# main_scheme.net
KiCad netlist of a schematic drawn in Altium Designer
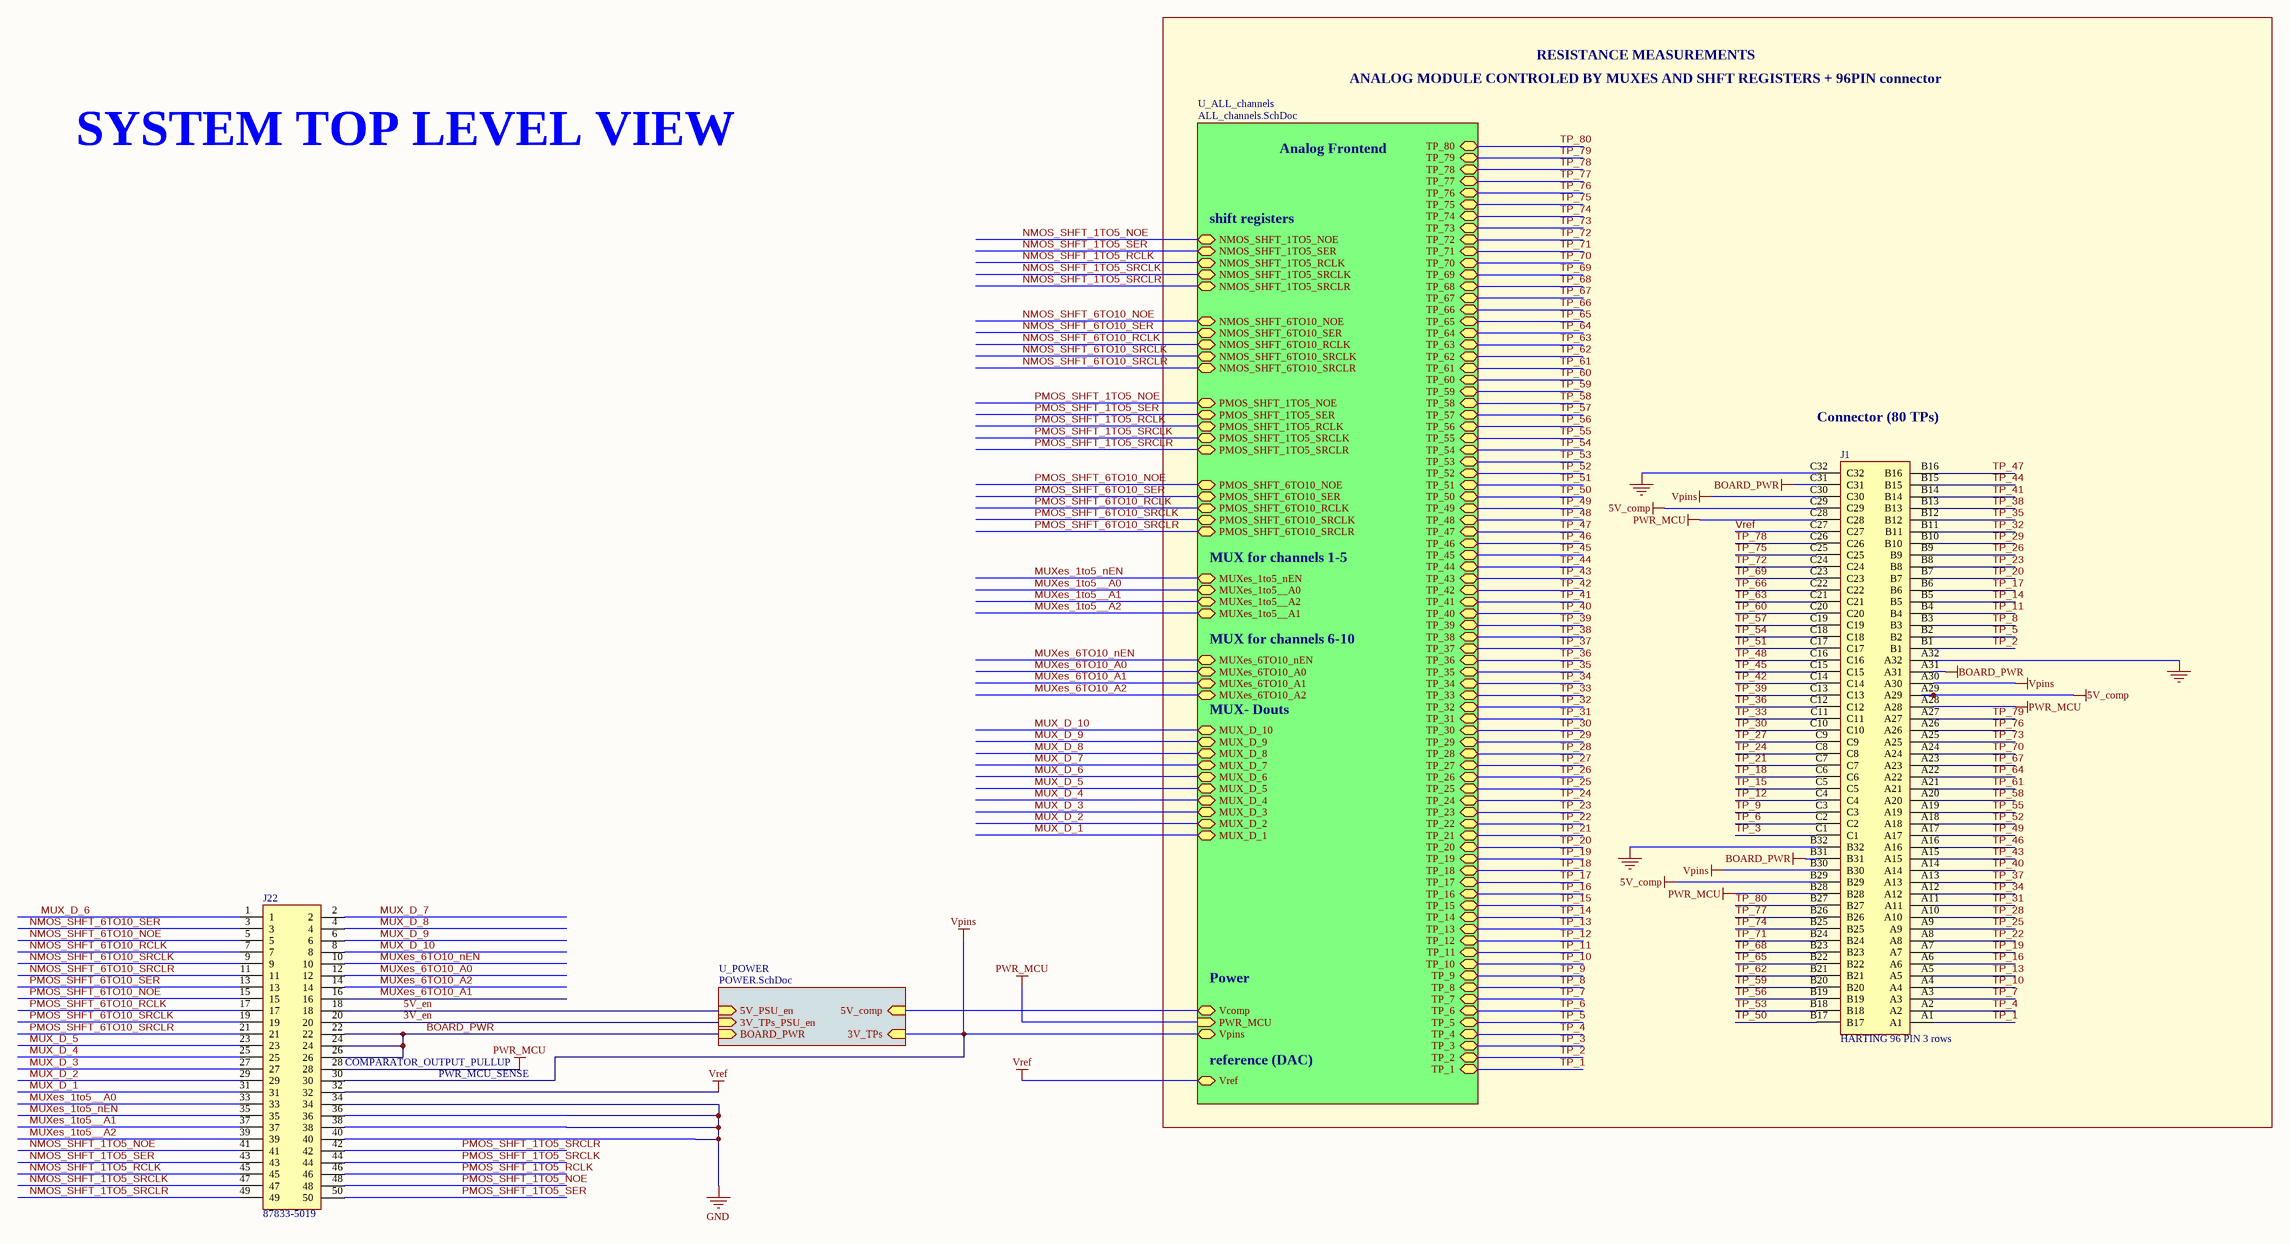
[diagram p0: main_scheme.SchDoc]

(export (version "E")
  (design (tool "Eeschema 10.0.6"))
  (components
    (comp (ref "J1")
      (value "HARTING 96 PIN 3 rows")
      (footprint "PcbLib1:09033966921")
      (description "Connector")
      (fields
        (field (name "MANUFACTURER_PART_NUMBER") "09033966921")
        (field (name "MOUSER PART NUMBER") "617-09-03-396-6921")
      )
      (libsource (lib "Schlib1") (part "HARTING 96 PIN 3 rows"))
    )
    (comp (ref "J22")
      (value "87833-5019")
      (footprint "SamacSys:SHDRRA50W55P200_2X25_5265X640X630P")
      (description "Connector")
      (fields (field (name "MOUSER PART NUMBER") "538-87833-5019"))
      (libsource (lib "*") (part "87833-5019"))
    )
  )
  (nets
    (net (code "1") (name "/3V_en") (class "Default")
      (node (ref "J22") (pin "20") (pinfunction "20_20") (pintype "passive"))
    )
    (net (code "3") (name "/5V_en") (class "Default")
      (node (ref "J22") (pin "18") (pinfunction "18_18") (pintype "passive"))
    )
    (net (code "4") (name "/MUX_D_1") (class "Default")
      (node (ref "J22") (pin "31") (pinfunction "31_31") (pintype "passive"))
    )
    (net (code "5") (name "/MUX_D_2") (class "Default")
      (node (ref "J22") (pin "29") (pinfunction "29_29") (pintype "passive"))
    )
    (net (code "6") (name "/MUX_D_3") (class "Default")
      (node (ref "J22") (pin "27") (pinfunction "27_27") (pintype "passive"))
    )
    (net (code "7") (name "/MUX_D_4") (class "Default")
      (node (ref "J22") (pin "25") (pinfunction "25_25") (pintype "passive"))
    )
    (net (code "8") (name "/MUX_D_5") (class "Default")
      (node (ref "J22") (pin "23") (pinfunction "23_23") (pintype "passive"))
    )
    (net (code "9") (name "/MUX_D_6") (class "Default")
      (node (ref "J22") (pin "1") (pinfunction "1_1") (pintype "passive"))
    )
    (net (code "10") (name "/MUX_D_7") (class "Default")
      (node (ref "J22") (pin "2") (pinfunction "2_2") (pintype "passive"))
    )
    (net (code "11") (name "/MUX_D_8") (class "Default")
      (node (ref "J22") (pin "4") (pinfunction "4_4") (pintype "passive"))
    )
    (net (code "12") (name "/MUX_D_9") (class "Default")
      (node (ref "J22") (pin "6") (pinfunction "6_6") (pintype "passive"))
    )
    (net (code "13") (name "/MUX_D_10") (class "Default")
      (node (ref "J22") (pin "8") (pinfunction "8_8") (pintype "passive"))
    )
    (net (code "14") (name "/MUXes_1to5__A0") (class "Default")
      (node (ref "J22") (pin "33") (pinfunction "33_33") (pintype "passive"))
    )
    (net (code "15") (name "/MUXes_1to5__A1") (class "Default")
      (node (ref "J22") (pin "37") (pinfunction "37_37") (pintype "passive"))
    )
    (net (code "16") (name "/MUXes_1to5__A2") (class "Default")
      (node (ref "J22") (pin "39") (pinfunction "39_39") (pintype "passive"))
    )
    (net (code "17") (name "/MUXes_1to5_nEN") (class "Default")
      (node (ref "J22") (pin "35") (pinfunction "35_35") (pintype "passive"))
    )
    (net (code "18") (name "/MUXes_6TO10_A0") (class "Default")
      (node (ref "J22") (pin "12") (pinfunction "12_12") (pintype "passive"))
    )
    (net (code "19") (name "/MUXes_6TO10_A1") (class "Default")
      (node (ref "J22") (pin "16") (pinfunction "16_16") (pintype "passive"))
    )
    (net (code "20") (name "/MUXes_6TO10_A2") (class "Default")
      (node (ref "J22") (pin "14") (pinfunction "14_14") (pintype "passive"))
    )
    (net (code "21") (name "/MUXes_6TO10_nEN") (class "Default")
      (node (ref "J22") (pin "10") (pinfunction "10_10") (pintype "passive"))
    )
    (net (code "22") (name "/NMOS_SHFT_1TO5_NOE") (class "Default")
      (node (ref "J22") (pin "41") (pinfunction "41_41") (pintype "passive"))
    )
    (net (code "23") (name "/NMOS_SHFT_1TO5_RCLK") (class "Default")
      (node (ref "J22") (pin "45") (pinfunction "45_45") (pintype "passive"))
    )
    (net (code "24") (name "/NMOS_SHFT_1TO5_SER") (class "Default")
      (node (ref "J22") (pin "43") (pinfunction "43_43") (pintype "passive"))
    )
    (net (code "25") (name "/NMOS_SHFT_1TO5_SRCLK") (class "Default")
      (node (ref "J22") (pin "47") (pinfunction "47_47") (pintype "passive"))
    )
    (net (code "26") (name "/NMOS_SHFT_1TO5_SRCLR") (class "Default")
      (node (ref "J22") (pin "49") (pinfunction "49_49") (pintype "passive"))
    )
    (net (code "27") (name "/NMOS_SHFT_6TO10_NOE") (class "Default")
      (node (ref "J22") (pin "5") (pinfunction "5_5") (pintype "passive"))
    )
    (net (code "28") (name "/NMOS_SHFT_6TO10_RCLK") (class "Default")
      (node (ref "J22") (pin "7") (pinfunction "7_7") (pintype "passive"))
    )
    (net (code "29") (name "/NMOS_SHFT_6TO10_SER") (class "Default")
      (node (ref "J22") (pin "3") (pinfunction "3_3") (pintype "passive"))
    )
    (net (code "30") (name "/NMOS_SHFT_6TO10_SRCLK") (class "Default")
      (node (ref "J22") (pin "9") (pinfunction "9_9") (pintype "passive"))
    )
    (net (code "31") (name "/NMOS_SHFT_6TO10_SRCLR") (class "Default")
      (node (ref "J22") (pin "11") (pinfunction "11_11") (pintype "passive"))
    )
    (net (code "32") (name "/PMOS_SHFT_1TO5_NOE") (class "Default")
      (node (ref "J22") (pin "48") (pinfunction "48_48") (pintype "passive"))
    )
    (net (code "33") (name "/PMOS_SHFT_1TO5_RCLK") (class "Default")
      (node (ref "J22") (pin "46") (pinfunction "46_46") (pintype "passive"))
    )
    (net (code "34") (name "/PMOS_SHFT_1TO5_SER") (class "Default")
      (node (ref "J22") (pin "50") (pinfunction "50_50") (pintype "passive"))
    )
    (net (code "35") (name "/PMOS_SHFT_1TO5_SRCLK") (class "Default")
      (node (ref "J22") (pin "44") (pinfunction "44_44") (pintype "passive"))
    )
    (net (code "36") (name "/PMOS_SHFT_1TO5_SRCLR") (class "Default")
      (node (ref "J22") (pin "42") (pinfunction "42_42") (pintype "passive"))
    )
    (net (code "37") (name "/PMOS_SHFT_6TO10_NOE") (class "Default")
      (node (ref "J22") (pin "15") (pinfunction "15_15") (pintype "passive"))
    )
    (net (code "38") (name "/PMOS_SHFT_6TO10_RCLK") (class "Default")
      (node (ref "J22") (pin "17") (pinfunction "17_17") (pintype "passive"))
    )
    (net (code "39") (name "/PMOS_SHFT_6TO10_SER") (class "Default")
      (node (ref "J22") (pin "13") (pinfunction "13_13") (pintype "passive"))
    )
    (net (code "40") (name "/PMOS_SHFT_6TO10_SRCLK") (class "Default")
      (node (ref "J22") (pin "19") (pinfunction "19_19") (pintype "passive"))
    )
    (net (code "41") (name "/PMOS_SHFT_6TO10_SRCLR") (class "Default")
      (node (ref "J22") (pin "21") (pinfunction "21_21") (pintype "passive"))
    )
    (net (code "42") (name "/TP_1") (class "Default")
      (node (ref "J1") (pin "A1") (pinfunction "A1_A1") (pintype "passive"))
    )
    (net (code "43") (name "/TP_2") (class "Default")
      (node (ref "J1") (pin "B1") (pinfunction "B1_B1") (pintype "passive"))
    )
    (net (code "44") (name "/TP_3") (class "Default")
      (node (ref "J1") (pin "C1") (pinfunction "C1_C1") (pintype "passive"))
    )
    (net (code "45") (name "/TP_4") (class "Default")
      (node (ref "J1") (pin "A2") (pinfunction "A2_A2") (pintype "passive"))
    )
    (net (code "46") (name "/TP_5") (class "Default")
      (node (ref "J1") (pin "B2") (pinfunction "B2_B2") (pintype "passive"))
    )
    (net (code "47") (name "/TP_6") (class "Default")
      (node (ref "J1") (pin "C2") (pinfunction "C2_C2") (pintype "passive"))
    )
    (net (code "48") (name "/TP_7") (class "Default")
      (node (ref "J1") (pin "A3") (pinfunction "A3_A3") (pintype "passive"))
    )
    (net (code "49") (name "/TP_8") (class "Default")
      (node (ref "J1") (pin "B3") (pinfunction "B3_B3") (pintype "passive"))
    )
    (net (code "50") (name "/TP_9") (class "Default")
      (node (ref "J1") (pin "C3") (pinfunction "C3_C3") (pintype "passive"))
    )
    (net (code "51") (name "/TP_10") (class "Default")
      (node (ref "J1") (pin "A4") (pinfunction "A4_A4") (pintype "passive"))
    )
    (net (code "52") (name "/TP_11") (class "Default")
      (node (ref "J1") (pin "B4") (pinfunction "B4_B4") (pintype "passive"))
    )
    (net (code "53") (name "/TP_12") (class "Default")
      (node (ref "J1") (pin "C4") (pinfunction "C4_C4") (pintype "passive"))
    )
    (net (code "54") (name "/TP_13") (class "Default")
      (node (ref "J1") (pin "A5") (pinfunction "A5_A5") (pintype "passive"))
    )
    (net (code "55") (name "/TP_14") (class "Default")
      (node (ref "J1") (pin "B5") (pinfunction "B5_B5") (pintype "passive"))
    )
    (net (code "56") (name "/TP_15") (class "Default")
      (node (ref "J1") (pin "C5") (pinfunction "C5_C5") (pintype "passive"))
    )
    (net (code "57") (name "/TP_16") (class "Default")
      (node (ref "J1") (pin "A6") (pinfunction "A6_A6") (pintype "passive"))
    )
    (net (code "58") (name "/TP_17") (class "Default")
      (node (ref "J1") (pin "B6") (pinfunction "B6_B6") (pintype "passive"))
    )
    (net (code "59") (name "/TP_18") (class "Default")
      (node (ref "J1") (pin "C6") (pinfunction "C6_C6") (pintype "passive"))
    )
    (net (code "60") (name "/TP_19") (class "Default")
      (node (ref "J1") (pin "A7") (pinfunction "A7_A7") (pintype "passive"))
    )
    (net (code "61") (name "/TP_20") (class "Default")
      (node (ref "J1") (pin "B7") (pinfunction "B7_B7") (pintype "passive"))
    )
    (net (code "62") (name "/TP_21") (class "Default")
      (node (ref "J1") (pin "C7") (pinfunction "C7_C7") (pintype "passive"))
    )
    (net (code "63") (name "/TP_22") (class "Default")
      (node (ref "J1") (pin "A8") (pinfunction "A8_A8") (pintype "passive"))
    )
    (net (code "64") (name "/TP_23") (class "Default")
      (node (ref "J1") (pin "B8") (pinfunction "B8_B8") (pintype "passive"))
    )
    (net (code "65") (name "/TP_24") (class "Default")
      (node (ref "J1") (pin "C8") (pinfunction "C8_C8") (pintype "passive"))
    )
    (net (code "66") (name "/TP_25") (class "Default")
      (node (ref "J1") (pin "A9") (pinfunction "A9_A9") (pintype "passive"))
    )
    (net (code "67") (name "/TP_26") (class "Default")
      (node (ref "J1") (pin "B9") (pinfunction "B9_B9") (pintype "passive"))
    )
    (net (code "68") (name "/TP_27") (class "Default")
      (node (ref "J1") (pin "C9") (pinfunction "C9_C9") (pintype "passive"))
    )
    (net (code "69") (name "/TP_28") (class "Default")
      (node (ref "J1") (pin "A10") (pinfunction "A10_A10") (pintype "passive"))
    )
    (net (code "70") (name "/TP_29") (class "Default")
      (node (ref "J1") (pin "B10") (pinfunction "B10_B10") (pintype "passive"))
    )
    (net (code "71") (name "/TP_30") (class "Default")
      (node (ref "J1") (pin "C10") (pinfunction "C10_C10") (pintype "passive"))
    )
    (net (code "72") (name "/TP_31") (class "Default")
      (node (ref "J1") (pin "A11") (pinfunction "A11_A11") (pintype "passive"))
    )
    (net (code "73") (name "/TP_32") (class "Default")
      (node (ref "J1") (pin "B11") (pinfunction "B11_B11") (pintype "passive"))
    )
    (net (code "74") (name "/TP_33") (class "Default")
      (node (ref "J1") (pin "C11") (pinfunction "C11_C11") (pintype "passive"))
    )
    (net (code "75") (name "/TP_34") (class "Default")
      (node (ref "J1") (pin "A12") (pinfunction "A12_A12") (pintype "passive"))
    )
    (net (code "76") (name "/TP_35") (class "Default")
      (node (ref "J1") (pin "B12") (pinfunction "B12_B12") (pintype "passive"))
    )
    (net (code "77") (name "/TP_36") (class "Default")
      (node (ref "J1") (pin "C12") (pinfunction "C12_C12") (pintype "passive"))
    )
    (net (code "78") (name "/TP_37") (class "Default")
      (node (ref "J1") (pin "A13") (pinfunction "A13_A13") (pintype "passive"))
    )
    (net (code "79") (name "/TP_38") (class "Default")
      (node (ref "J1") (pin "B13") (pinfunction "B13_B13") (pintype "passive"))
    )
    (net (code "80") (name "/TP_39") (class "Default")
      (node (ref "J1") (pin "C13") (pinfunction "C13_C13") (pintype "passive"))
    )
    (net (code "81") (name "/TP_40") (class "Default")
      (node (ref "J1") (pin "A14") (pinfunction "A14_A14") (pintype "passive"))
    )
    (net (code "82") (name "/TP_41") (class "Default")
      (node (ref "J1") (pin "B14") (pinfunction "B14_B14") (pintype "passive"))
    )
    (net (code "83") (name "/TP_42") (class "Default")
      (node (ref "J1") (pin "C14") (pinfunction "C14_C14") (pintype "passive"))
    )
    (net (code "84") (name "/TP_43") (class "Default")
      (node (ref "J1") (pin "A15") (pinfunction "A15_A15") (pintype "passive"))
    )
    (net (code "85") (name "/TP_44") (class "Default")
      (node (ref "J1") (pin "B15") (pinfunction "B15_B15") (pintype "passive"))
    )
    (net (code "86") (name "/TP_45") (class "Default")
      (node (ref "J1") (pin "C15") (pinfunction "C15_C15") (pintype "passive"))
    )
    (net (code "87") (name "/TP_46") (class "Default")
      (node (ref "J1") (pin "A16") (pinfunction "A16_A16") (pintype "passive"))
    )
    (net (code "88") (name "/TP_47") (class "Default")
      (node (ref "J1") (pin "B16") (pinfunction "B16_B16") (pintype "passive"))
    )
    (net (code "89") (name "/TP_48") (class "Default")
      (node (ref "J1") (pin "C16") (pinfunction "C16_C16") (pintype "passive"))
    )
    (net (code "90") (name "/TP_49") (class "Default")
      (node (ref "J1") (pin "A17") (pinfunction "A17_A17") (pintype "passive"))
    )
    (net (code "91") (name "/TP_50") (class "Default")
      (node (ref "J1") (pin "B17") (pinfunction "B17_B17") (pintype "passive"))
    )
    (net (code "92") (name "/TP_51") (class "Default")
      (node (ref "J1") (pin "C17") (pinfunction "C17_C17") (pintype "passive"))
    )
    (net (code "93") (name "/TP_52") (class "Default")
      (node (ref "J1") (pin "A18") (pinfunction "A18_A18") (pintype "passive"))
    )
    (net (code "94") (name "/TP_53") (class "Default")
      (node (ref "J1") (pin "B18") (pinfunction "B18_B18") (pintype "passive"))
    )
    (net (code "95") (name "/TP_54") (class "Default")
      (node (ref "J1") (pin "C18") (pinfunction "C18_C18") (pintype "passive"))
    )
    (net (code "96") (name "/TP_55") (class "Default")
      (node (ref "J1") (pin "A19") (pinfunction "A19_A19") (pintype "passive"))
    )
    (net (code "97") (name "/TP_56") (class "Default")
      (node (ref "J1") (pin "B19") (pinfunction "B19_B19") (pintype "passive"))
    )
    (net (code "98") (name "/TP_57") (class "Default")
      (node (ref "J1") (pin "C19") (pinfunction "C19_C19") (pintype "passive"))
    )
    (net (code "99") (name "/TP_58") (class "Default")
      (node (ref "J1") (pin "A20") (pinfunction "A20_A20") (pintype "passive"))
    )
    (net (code "100") (name "/TP_59") (class "Default")
      (node (ref "J1") (pin "B20") (pinfunction "B20_B20") (pintype "passive"))
    )
    (net (code "101") (name "/TP_60") (class "Default")
      (node (ref "J1") (pin "C20") (pinfunction "C20_C20") (pintype "passive"))
    )
    (net (code "102") (name "/TP_61") (class "Default")
      (node (ref "J1") (pin "A21") (pinfunction "A21_A21") (pintype "passive"))
    )
    (net (code "103") (name "/TP_62") (class "Default")
      (node (ref "J1") (pin "B21") (pinfunction "B21_B21") (pintype "passive"))
    )
    (net (code "104") (name "/TP_63") (class "Default")
      (node (ref "J1") (pin "C21") (pinfunction "C21_C21") (pintype "passive"))
    )
    (net (code "105") (name "/TP_64") (class "Default")
      (node (ref "J1") (pin "A22") (pinfunction "A22_A22") (pintype "passive"))
    )
    (net (code "106") (name "/TP_65") (class "Default")
      (node (ref "J1") (pin "B22") (pinfunction "B22_B22") (pintype "passive"))
    )
    (net (code "107") (name "/TP_66") (class "Default")
      (node (ref "J1") (pin "C22") (pinfunction "C22_C22") (pintype "passive"))
    )
    (net (code "108") (name "/TP_67") (class "Default")
      (node (ref "J1") (pin "A23") (pinfunction "A23_A23") (pintype "passive"))
    )
    (net (code "109") (name "/TP_68") (class "Default")
      (node (ref "J1") (pin "B23") (pinfunction "B23_B23") (pintype "passive"))
    )
    (net (code "110") (name "/TP_69") (class "Default")
      (node (ref "J1") (pin "C23") (pinfunction "C23_C23") (pintype "passive"))
    )
    (net (code "111") (name "/TP_70") (class "Default")
      (node (ref "J1") (pin "A24") (pinfunction "A24_A24") (pintype "passive"))
    )
    (net (code "112") (name "/TP_71") (class "Default")
      (node (ref "J1") (pin "B24") (pinfunction "B24_B24") (pintype "passive"))
    )
    (net (code "113") (name "/TP_72") (class "Default")
      (node (ref "J1") (pin "C24") (pinfunction "C24_C24") (pintype "passive"))
    )
    (net (code "114") (name "/TP_73") (class "Default")
      (node (ref "J1") (pin "A25") (pinfunction "A25_A25") (pintype "passive"))
    )
    (net (code "115") (name "/TP_74") (class "Default")
      (node (ref "J1") (pin "B25") (pinfunction "B25_B25") (pintype "passive"))
    )
    (net (code "116") (name "/TP_75") (class "Default")
      (node (ref "J1") (pin "C25") (pinfunction "C25_C25") (pintype "passive"))
    )
    (net (code "117") (name "/TP_76") (class "Default")
      (node (ref "J1") (pin "A26") (pinfunction "A26_A26") (pintype "passive"))
    )
    (net (code "118") (name "/TP_77") (class "Default")
      (node (ref "J1") (pin "B26") (pinfunction "B26_B26") (pintype "passive"))
    )
    (net (code "119") (name "/TP_78") (class "Default")
      (node (ref "J1") (pin "C26") (pinfunction "C26_C26") (pintype "passive"))
    )
    (net (code "120") (name "/TP_79") (class "Default")
      (node (ref "J1") (pin "A27") (pinfunction "A27_A27") (pintype "passive"))
    )
    (net (code "121") (name "/TP_80") (class "Default")
      (node (ref "J1") (pin "B27") (pinfunction "B27_B27") (pintype "passive"))
    )
    (net (code "122") (name "5V_comp") (class "Default")
      (node (ref "J1") (pin "A29") (pinfunction "A29_A29") (pintype "passive"))
      (node (ref "J1") (pin "B29") (pinfunction "B29_B29") (pintype "passive"))
      (node (ref "J1") (pin "C29") (pinfunction "C29_C29") (pintype "passive"))
    )
    (net (code "123") (name "BOARD_PWR") (class "Default")
      (node (ref "J1") (pin "A31") (pinfunction "A31_A31") (pintype "passive"))
      (node (ref "J1") (pin "B31") (pinfunction "B31_B31") (pintype "passive"))
      (node (ref "J1") (pin "C31") (pinfunction "C31_C31") (pintype "passive"))
      (node (ref "J22") (pin "22") (pinfunction "22_22") (pintype "passive"))
      (node (ref "J22") (pin "24") (pinfunction "24_24") (pintype "passive"))
      (node (ref "J22") (pin "26") (pinfunction "26_26") (pintype "passive"))
    )
    (net (code "124") (name "GND") (class "Default")
      (node (ref "J1") (pin "A32") (pinfunction "A32_A32") (pintype "passive"))
      (node (ref "J1") (pin "B32") (pinfunction "B32_B32") (pintype "passive"))
      (node (ref "J1") (pin "C32") (pinfunction "C32_C32") (pintype "passive"))
      (node (ref "J22") (pin "34") (pinfunction "34_34") (pintype "passive"))
      (node (ref "J22") (pin "36") (pinfunction "36_36") (pintype "passive"))
      (node (ref "J22") (pin "38") (pinfunction "38_38") (pintype "passive"))
      (node (ref "J22") (pin "40") (pinfunction "40_40") (pintype "passive"))
    )
    (net (code "125") (name "PWR_MCU") (class "Default")
      (node (ref "J1") (pin "A28") (pinfunction "A28_A28") (pintype "passive"))
      (node (ref "J1") (pin "B28") (pinfunction "B28_B28") (pintype "passive"))
      (node (ref "J1") (pin "C28") (pinfunction "C28_C28") (pintype "passive"))
      (node (ref "J22") (pin "28") (pinfunction "28_28") (pintype "passive"))
    )
    (net (code "126") (name "Vpins") (class "Default")
      (node (ref "J1") (pin "A30") (pinfunction "A30_A30") (pintype "passive"))
      (node (ref "J1") (pin "B30") (pinfunction "B30_B30") (pintype "passive"))
      (node (ref "J1") (pin "C30") (pinfunction "C30_C30") (pintype "passive"))
      (node (ref "J22") (pin "30") (pinfunction "30_30") (pintype "passive"))
    )
    (net (code "127") (name "Vref") (class "Default")
      (node (ref "J1") (pin "C27") (pinfunction "C27_C27") (pintype "passive"))
      (node (ref "J22") (pin "32") (pinfunction "32_32") (pintype "passive"))
    )
  )
)
